# instr_amp_ex.net
KiCad netlist of a schematic drawn in EAGLE
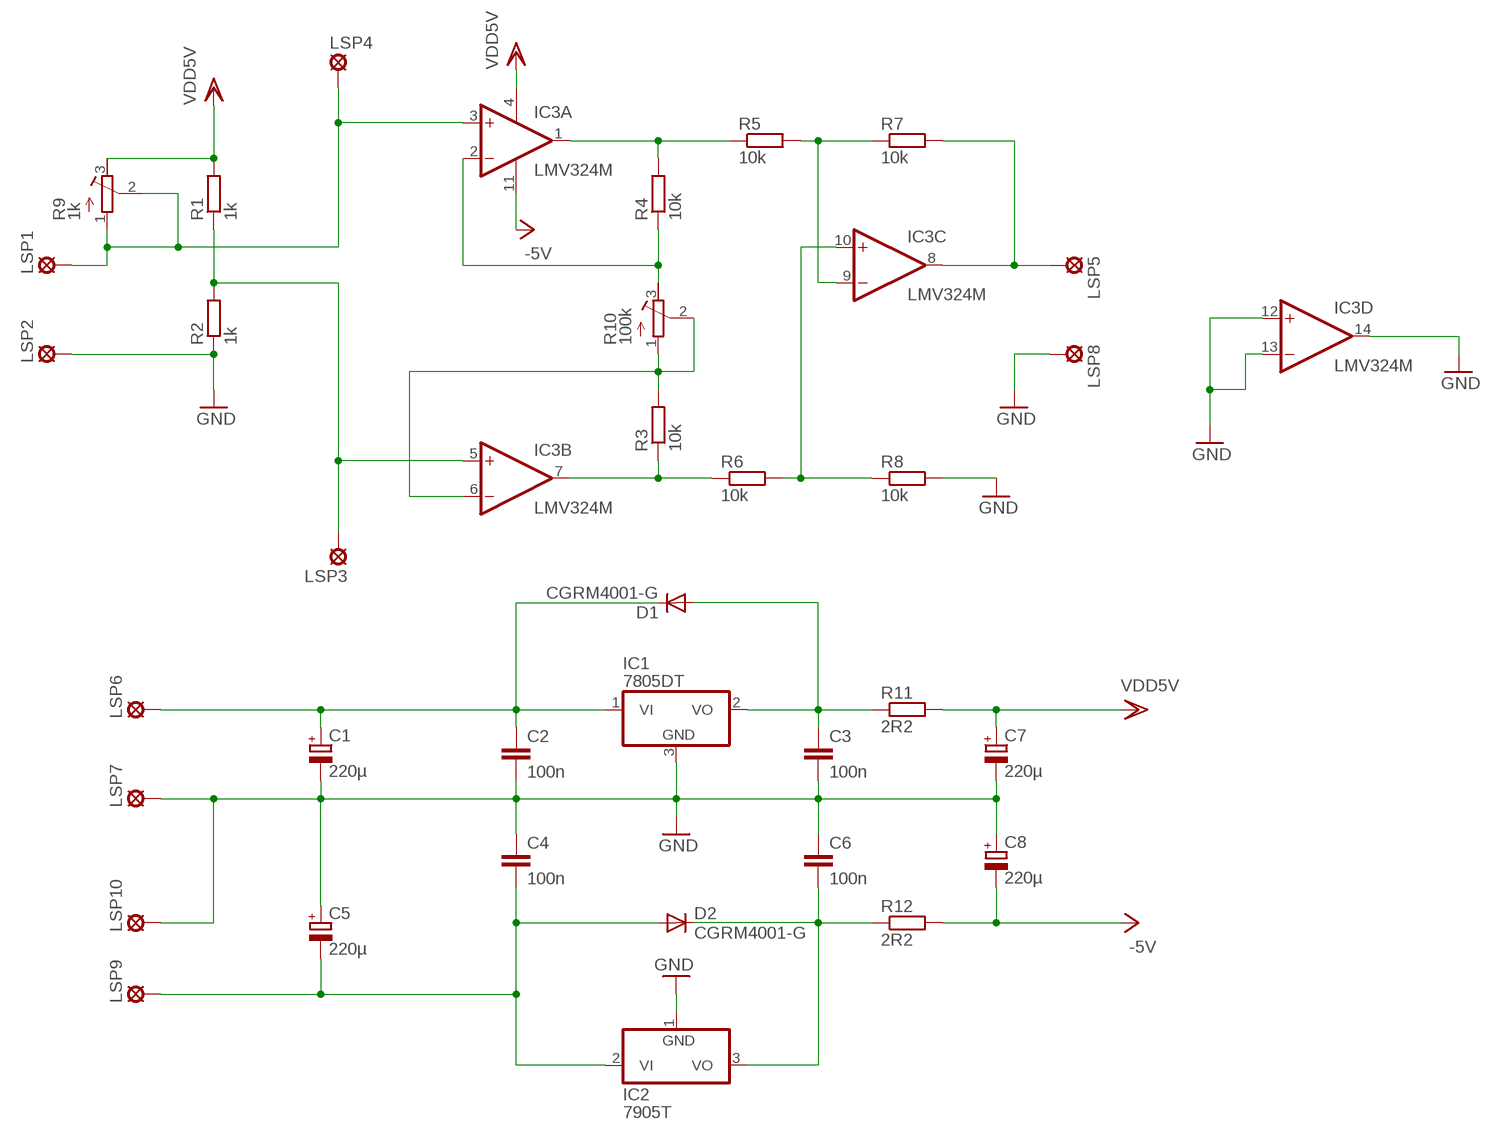
[diagram p0: schematic, sheet 1]

(export (version "E")
  (design (tool "Eeschema 10.0.6"))
  (components
    (comp (ref "C1")
      (value "220µ")
      (footprint "eagle-import:085CS_1AW")
      (libsource (lib "eagle-import") (part "CPOL-EU085CS-1AW"))
    )
    (comp (ref "C2")
      (value "100n")
      (footprint "eagle-import:C1206K")
      (libsource (lib "eagle-import") (part "C-EUC1206K"))
    )
    (comp (ref "C3")
      (value "100n")
      (footprint "eagle-import:C1206K")
      (libsource (lib "eagle-import") (part "C-EUC1206K"))
    )
    (comp (ref "C4")
      (value "100n")
      (footprint "eagle-import:C1206K")
      (libsource (lib "eagle-import") (part "C-EUC1206K"))
    )
    (comp (ref "C5")
      (value "220µ")
      (footprint "eagle-import:085CS_1AW")
      (libsource (lib "eagle-import") (part "CPOL-EU085CS-1AW"))
    )
    (comp (ref "C6")
      (value "100n")
      (footprint "eagle-import:C1206K")
      (libsource (lib "eagle-import") (part "C-EUC1206K"))
    )
    (comp (ref "C7")
      (value "220µ")
      (footprint "eagle-import:085CS_1AW")
      (libsource (lib "eagle-import") (part "CPOL-EU085CS-1AW"))
    )
    (comp (ref "C8")
      (value "220µ")
      (footprint "eagle-import:085CS_1AW")
      (libsource (lib "eagle-import") (part "CPOL-EU085CS-1AW"))
    )
    (comp (ref "D1")
      (value "CGRM4001-G")
      (footprint "eagle-import:SOD-123_MINI-SMA")
      (libsource (lib "eagle-import") (part "CGRM400-G1"))
    )
    (comp (ref "D2")
      (value "CGRM4001-G")
      (footprint "eagle-import:SOD-123_MINI-SMA")
      (libsource (lib "eagle-import") (part "CGRM400-G1"))
    )
    (comp (ref "IC1")
      (value "7805DT")
      (footprint "eagle-import:TO252")
      (libsource (lib "eagle-import") (part "78DT05"))
    )
    (comp (ref "IC2")
      (value "7905T")
      (footprint "eagle-import:TO220H")
      (libsource (lib "eagle-import") (part "79T05"))
    )
    (comp (ref "IC3")
      (value "LMV324M")
      (footprint "eagle-import:SO14")
      (libsource (lib "eagle-import") (part "LMV324?M"))
    )
    (comp (ref "LSP1")
      (value "LSP13")
      (footprint "eagle-import:LSP13")
      (libsource (lib "eagle-import") (part "LSP13"))
    )
    (comp (ref "LSP2")
      (value "LSP13")
      (footprint "eagle-import:LSP13")
      (libsource (lib "eagle-import") (part "LSP13"))
    )
    (comp (ref "LSP3")
      (value "LSP13")
      (footprint "eagle-import:LSP13")
      (libsource (lib "eagle-import") (part "LSP13"))
    )
    (comp (ref "LSP4")
      (value "LSP13")
      (footprint "eagle-import:LSP13")
      (libsource (lib "eagle-import") (part "LSP13"))
    )
    (comp (ref "LSP5")
      (value "LSP13")
      (footprint "eagle-import:LSP13")
      (libsource (lib "eagle-import") (part "LSP13"))
    )
    (comp (ref "LSP6")
      (value "LSP13")
      (footprint "eagle-import:LSP13")
      (libsource (lib "eagle-import") (part "LSP13"))
    )
    (comp (ref "LSP7")
      (value "LSP13")
      (footprint "eagle-import:LSP13")
      (libsource (lib "eagle-import") (part "LSP13"))
    )
    (comp (ref "LSP8")
      (value "LSP13")
      (footprint "eagle-import:LSP13")
      (libsource (lib "eagle-import") (part "LSP13"))
    )
    (comp (ref "LSP9")
      (value "LSP13")
      (footprint "eagle-import:LSP13")
      (libsource (lib "eagle-import") (part "LSP13"))
    )
    (comp (ref "LSP10")
      (value "LSP13")
      (footprint "eagle-import:LSP13")
      (libsource (lib "eagle-import") (part "LSP13"))
    )
    (comp (ref "R1")
      (value "1k")
      (footprint "eagle-import:R1206")
      (libsource (lib "eagle-import") (part "R-EU_R1206"))
    )
    (comp (ref "R2")
      (value "1k")
      (footprint "eagle-import:R1206")
      (libsource (lib "eagle-import") (part "R-EU_R1206"))
    )
    (comp (ref "R3")
      (value "10k")
      (footprint "eagle-import:R1206")
      (libsource (lib "eagle-import") (part "R-EU_R1206"))
    )
    (comp (ref "R4")
      (value "10k")
      (footprint "eagle-import:R1206")
      (libsource (lib "eagle-import") (part "R-EU_R1206"))
    )
    (comp (ref "R5")
      (value "10k")
      (footprint "eagle-import:R1206")
      (libsource (lib "eagle-import") (part "R-EU_R1206"))
    )
    (comp (ref "R6")
      (value "10k")
      (footprint "eagle-import:R1206")
      (libsource (lib "eagle-import") (part "R-EU_R1206"))
    )
    (comp (ref "R7")
      (value "10k")
      (footprint "eagle-import:R1206")
      (libsource (lib "eagle-import") (part "R-EU_R1206"))
    )
    (comp (ref "R8")
      (value "10k")
      (footprint "eagle-import:R1206")
      (libsource (lib "eagle-import") (part "R-EU_R1206"))
    )
    (comp (ref "R9")
      (value "1k")
      (footprint "eagle-import:RTRIM3224W")
      (libsource (lib "eagle-import") (part "R-TRIMM3224W"))
    )
    (comp (ref "R10")
      (value "100k")
      (footprint "eagle-import:RTRIM3224W")
      (libsource (lib "eagle-import") (part "R-TRIMM3224W"))
    )
    (comp (ref "R11")
      (value "2R2")
      (footprint "eagle-import:R1206")
      (libsource (lib "eagle-import") (part "R-EU_R1206"))
    )
    (comp (ref "R12")
      (value "2R2")
      (footprint "eagle-import:R1206")
      (libsource (lib "eagle-import") (part "R-EU_R1206"))
    )
  )
  (nets
    (net (code "1") (name "-5V") (class "Default")
      (node (ref "C8") (pin "-") (pinfunction "-_-") (pintype "passive"))
      (node (ref "IC3") (pin "11") (pinfunction "V-_11") (pintype "power_in"))
      (node (ref "R12") (pin "2") (pinfunction "2_2") (pintype "passive"))
    )
    (net (code "2") (name "GND") (class "Default")
      (node (ref "C1") (pin "-") (pinfunction "-_-") (pintype "passive"))
      (node (ref "C2") (pin "2") (pinfunction "2_2") (pintype "passive"))
      (node (ref "C3") (pin "2") (pinfunction "2_2") (pintype "passive"))
      (node (ref "C4") (pin "1") (pinfunction "1_1") (pintype "passive"))
      (node (ref "C5") (pin "+") (pinfunction "+_+") (pintype "passive"))
      (node (ref "C6") (pin "1") (pinfunction "1_1") (pintype "passive"))
      (node (ref "C7") (pin "-") (pinfunction "-_-") (pintype "passive"))
      (node (ref "C8") (pin "+") (pinfunction "+_+") (pintype "passive"))
      (node (ref "IC1") (pin "3") (pinfunction "GND_3") (pintype "passive"))
      (node (ref "IC2") (pin "1") (pinfunction "GND_1") (pintype "passive"))
      (node (ref "IC3") (pin "12") (pinfunction "+IN_12") (pintype "input"))
      (node (ref "IC3") (pin "13") (pinfunction "-IN_13") (pintype "input"))
      (node (ref "IC3") (pin "14") (pinfunction "OUT_14") (pintype "output"))
      (node (ref "LSP10") (pin "MP") (pinfunction "MP_MP") (pintype "passive"))
      (node (ref "LSP2") (pin "MP") (pinfunction "MP_MP") (pintype "passive"))
      (node (ref "LSP7") (pin "MP") (pinfunction "MP_MP") (pintype "passive"))
      (node (ref "LSP8") (pin "MP") (pinfunction "MP_MP") (pintype "passive"))
      (node (ref "R2") (pin "1") (pinfunction "1_1") (pintype "passive"))
      (node (ref "R8") (pin "2") (pinfunction "2_2") (pintype "passive"))
    )
    (net (code "3") (name "Net-(IC1-VI)") (class "Default")
      (node (ref "C1") (pin "+") (pinfunction "+_+") (pintype "passive"))
      (node (ref "C2") (pin "1") (pinfunction "1_1") (pintype "passive"))
      (node (ref "D1") (pin "C") (pinfunction "C_C") (pintype "passive"))
      (node (ref "IC1") (pin "1") (pinfunction "VI_1") (pintype "input"))
      (node (ref "LSP6") (pin "MP") (pinfunction "MP_MP") (pintype "passive"))
    )
    (net (code "4") (name "Net-(IC1-VO)") (class "Default")
      (node (ref "C3") (pin "1") (pinfunction "1_1") (pintype "passive"))
      (node (ref "D1") (pin "A") (pinfunction "A_A") (pintype "passive"))
      (node (ref "IC1") (pin "2") (pinfunction "VO_2") (pintype "passive"))
      (node (ref "R11") (pin "1") (pinfunction "1_1") (pintype "passive"))
    )
    (net (code "5") (name "Net-(IC2-VI)") (class "Default")
      (node (ref "C4") (pin "2") (pinfunction "2_2") (pintype "passive"))
      (node (ref "C5") (pin "-") (pinfunction "-_-") (pintype "passive"))
      (node (ref "D2") (pin "A") (pinfunction "A_A") (pintype "passive"))
      (node (ref "IC2") (pin "2") (pinfunction "VI_2") (pintype "input"))
      (node (ref "LSP9") (pin "MP") (pinfunction "MP_MP") (pintype "passive"))
    )
    (net (code "6") (name "Net-(IC2-VO)") (class "Default")
      (node (ref "C6") (pin "2") (pinfunction "2_2") (pintype "passive"))
      (node (ref "D2") (pin "C") (pinfunction "C_C") (pintype "passive"))
      (node (ref "IC2") (pin "3") (pinfunction "VO_3") (pintype "passive"))
      (node (ref "R12") (pin "1") (pinfunction "1_1") (pintype "passive"))
    )
    (net (code "7") (name "Net-(IC3A-+IN)") (class "Default")
      (node (ref "IC3") (pin "3") (pinfunction "+IN_3") (pintype "input"))
      (node (ref "LSP1") (pin "MP") (pinfunction "MP_MP") (pintype "passive"))
      (node (ref "LSP4") (pin "MP") (pinfunction "MP_MP") (pintype "passive"))
      (node (ref "R9") (pin "1") (pinfunction "A_1") (pintype "passive"))
      (node (ref "R9") (pin "2") (pinfunction "S_2") (pintype "passive"))
    )
    (net (code "8") (name "Net-(IC3A--IN)") (class "Default")
      (node (ref "IC3") (pin "2") (pinfunction "-IN_2") (pintype "input"))
      (node (ref "R10") (pin "3") (pinfunction "E_3") (pintype "passive"))
      (node (ref "R4") (pin "1") (pinfunction "1_1") (pintype "passive"))
    )
    (net (code "9") (name "Net-(IC3A-OUT)") (class "Default")
      (node (ref "IC3") (pin "1") (pinfunction "OUT_1") (pintype "output"))
      (node (ref "R4") (pin "2") (pinfunction "2_2") (pintype "passive"))
      (node (ref "R5") (pin "1") (pinfunction "1_1") (pintype "passive"))
    )
    (net (code "10") (name "Net-(IC3B-+IN)") (class "Default")
      (node (ref "IC3") (pin "5") (pinfunction "+IN_5") (pintype "input"))
      (node (ref "LSP3") (pin "MP") (pinfunction "MP_MP") (pintype "passive"))
      (node (ref "R1") (pin "1") (pinfunction "1_1") (pintype "passive"))
      (node (ref "R2") (pin "2") (pinfunction "2_2") (pintype "passive"))
    )
    (net (code "11") (name "Net-(IC3B--IN)") (class "Default")
      (node (ref "IC3") (pin "6") (pinfunction "-IN_6") (pintype "input"))
      (node (ref "R10") (pin "1") (pinfunction "A_1") (pintype "passive"))
      (node (ref "R10") (pin "2") (pinfunction "S_2") (pintype "passive"))
      (node (ref "R3") (pin "2") (pinfunction "2_2") (pintype "passive"))
    )
    (net (code "12") (name "Net-(IC3B-OUT)") (class "Default")
      (node (ref "IC3") (pin "7") (pinfunction "OUT_7") (pintype "output"))
      (node (ref "R3") (pin "1") (pinfunction "1_1") (pintype "passive"))
      (node (ref "R6") (pin "1") (pinfunction "1_1") (pintype "passive"))
    )
    (net (code "13") (name "Net-(IC3C-+IN)") (class "Default")
      (node (ref "IC3") (pin "10") (pinfunction "+IN_10") (pintype "input"))
      (node (ref "R6") (pin "2") (pinfunction "2_2") (pintype "passive"))
      (node (ref "R8") (pin "1") (pinfunction "1_1") (pintype "passive"))
    )
    (net (code "14") (name "Net-(IC3C--IN)") (class "Default")
      (node (ref "IC3") (pin "9") (pinfunction "-IN_9") (pintype "input"))
      (node (ref "R5") (pin "2") (pinfunction "2_2") (pintype "passive"))
      (node (ref "R7") (pin "1") (pinfunction "1_1") (pintype "passive"))
    )
    (net (code "15") (name "Net-(IC3C-OUT)") (class "Default")
      (node (ref "IC3") (pin "8") (pinfunction "OUT_8") (pintype "output"))
      (node (ref "LSP5") (pin "MP") (pinfunction "MP_MP") (pintype "passive"))
      (node (ref "R7") (pin "2") (pinfunction "2_2") (pintype "passive"))
    )
    (net (code "16") (name "VDD5V") (class "Default")
      (node (ref "C7") (pin "+") (pinfunction "+_+") (pintype "passive"))
      (node (ref "IC3") (pin "4") (pinfunction "V+_4") (pintype "power_in"))
      (node (ref "R1") (pin "2") (pinfunction "2_2") (pintype "passive"))
      (node (ref "R11") (pin "2") (pinfunction "2_2") (pintype "passive"))
      (node (ref "R9") (pin "3") (pinfunction "E_3") (pintype "passive"))
    )
  )
)
